# clink.net
KiCad netlist of a schematic drawn in EAGLE
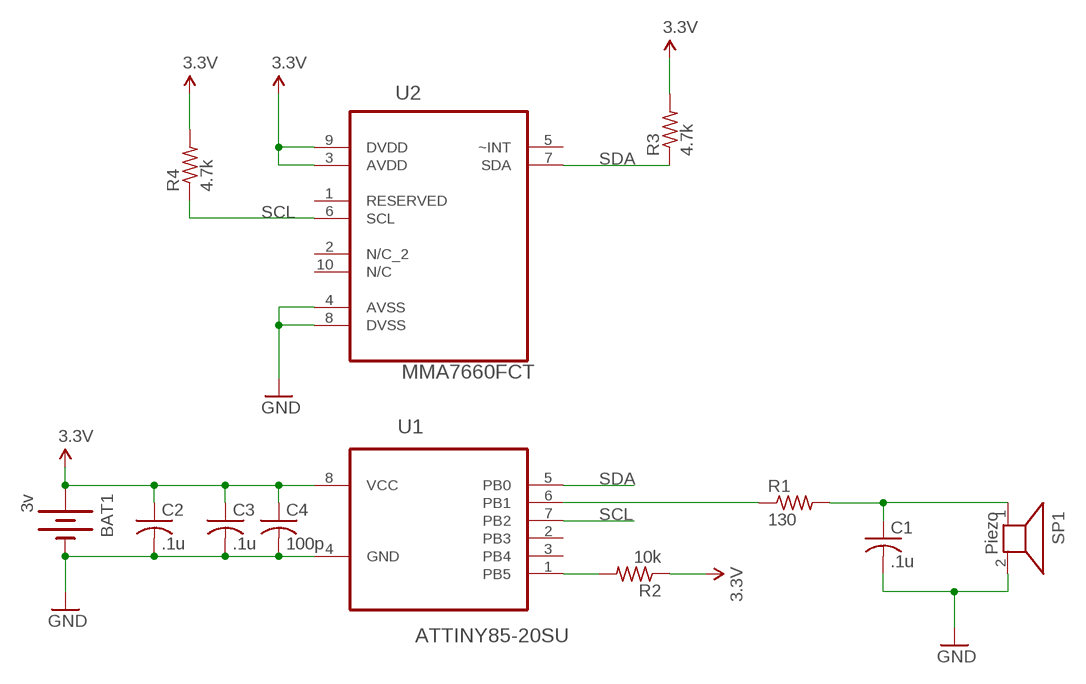
[diagram p0: schematic, sheet 1]

(export (version "E")
  (design (tool "Eeschema 10.0.6"))
  (components
    (comp (ref "BAT1")
      (value "3v")
      (footprint "eagle-import:BATTCON_20MM")
      (libsource (lib "eagle-import") (part "BATTERY20SMD"))
    )
    (comp (ref "C1")
      (value ".1u")
      (footprint "eagle-import:C0603")
      (libsource (lib "eagle-import") (part "C-USC0603"))
    )
    (comp (ref "C2")
      (value ".1u")
      (footprint "eagle-import:C0603")
      (libsource (lib "eagle-import") (part "C-USC0603"))
    )
    (comp (ref "C3")
      (value ".1u")
      (footprint "eagle-import:C0603")
      (libsource (lib "eagle-import") (part "C-USC0603"))
    )
    (comp (ref "C4")
      (value "100p")
      (footprint "eagle-import:C0603")
      (libsource (lib "eagle-import") (part "C-USC0603"))
    )
    (comp (ref "R1")
      (value "130")
      (footprint "eagle-import:R0603")
      (libsource (lib "eagle-import") (part "R-US_R0603"))
    )
    (comp (ref "R2")
      (value "10k")
      (footprint "eagle-import:R0603")
      (libsource (lib "eagle-import") (part "R-US_R0603"))
    )
    (comp (ref "R3")
      (value "4.7k")
      (footprint "eagle-import:R0603")
      (libsource (lib "eagle-import") (part "R-US_R0603"))
    )
    (comp (ref "R4")
      (value "4.7k")
      (footprint "eagle-import:R0603")
      (libsource (lib "eagle-import") (part "R-US_R0603"))
    )
    (comp (ref "SP1")
      (value "Piezo")
      (footprint "eagle-import:AL201P")
      (libsource (lib "eagle-import") (part "AL201P"))
    )
    (comp (ref "U1")
      (value "ATTINY85-20SU")
      (footprint "eagle-import:SOIC127P798X216-8N")
      (libsource (lib "eagle-import") (part "ATTINY85-20SU"))
    )
    (comp (ref "U2")
      (value "MMA7660FCT")
      (footprint "eagle-import:DFN300X300X100-10N")
      (libsource (lib "eagle-import") (part "MMA7660FCT"))
    )
  )
  (nets
    (net (code "1") (name "/SCL") (class "Default")
      (node (ref "R4") (pin "1") (pinfunction "1_1") (pintype "passive"))
      (node (ref "U1") (pin "7") (pinfunction "PB2_7") (pintype "bidirectional"))
      (node (ref "U2") (pin "6") (pinfunction "SCL_6") (pintype "input"))
    )
    (net (code "2") (name "/SDA") (class "Default")
      (node (ref "R3") (pin "1") (pinfunction "1_1") (pintype "passive"))
      (node (ref "U1") (pin "5") (pinfunction "PB0_5") (pintype "bidirectional"))
      (node (ref "U2") (pin "7") (pinfunction "SDA_7") (pintype "bidirectional"))
    )
    (net (code "3") (name "3.3V") (class "Default")
      (node (ref "BAT1") (pin "1") (pinfunction "+_1") (pintype "power_in"))
      (node (ref "C2") (pin "1") (pinfunction "1_1") (pintype "passive"))
      (node (ref "C3") (pin "1") (pinfunction "1_1") (pintype "passive"))
      (node (ref "C4") (pin "1") (pinfunction "1_1") (pintype "passive"))
      (node (ref "R2") (pin "1") (pinfunction "1_1") (pintype "passive"))
      (node (ref "R3") (pin "2") (pinfunction "2_2") (pintype "passive"))
      (node (ref "R4") (pin "2") (pinfunction "2_2") (pintype "passive"))
      (node (ref "U1") (pin "8") (pinfunction "VCC_8") (pintype "power_in"))
      (node (ref "U2") (pin "3") (pinfunction "AVDD_3") (pintype "power_in"))
      (node (ref "U2") (pin "9") (pinfunction "DVDD_9") (pintype "power_in"))
    )
    (net (code "4") (name "GND") (class "Default")
      (node (ref "BAT1") (pin "2") (pinfunction "-_2") (pintype "power_in"))
      (node (ref "C1") (pin "2") (pinfunction "2_2") (pintype "passive"))
      (node (ref "C2") (pin "2") (pinfunction "2_2") (pintype "passive"))
      (node (ref "C3") (pin "2") (pinfunction "2_2") (pintype "passive"))
      (node (ref "C4") (pin "2") (pinfunction "2_2") (pintype "passive"))
      (node (ref "SP1") (pin "2") (pinfunction "2_2") (pintype "passive"))
      (node (ref "U1") (pin "4") (pinfunction "GND_4") (pintype "passive"))
      (node (ref "U2") (pin "4") (pinfunction "AVSS_4") (pintype "power_in"))
      (node (ref "U2") (pin "8") (pinfunction "DVSS_8") (pintype "power_in"))
    )
    (net (code "5") (name "Net-(C1-Pad1)") (class "Default")
      (node (ref "C1") (pin "1") (pinfunction "1_1") (pintype "passive"))
      (node (ref "R1") (pin "2") (pinfunction "2_2") (pintype "passive"))
      (node (ref "SP1") (pin "1") (pinfunction "1_1") (pintype "passive"))
    )
    (net (code "6") (name "Net-(U1-PB1)") (class "Default")
      (node (ref "R1") (pin "1") (pinfunction "1_1") (pintype "passive"))
      (node (ref "U1") (pin "6") (pinfunction "PB1_6") (pintype "bidirectional"))
    )
    (net (code "7") (name "Net-(U1-PB5)") (class "Default")
      (node (ref "R2") (pin "2") (pinfunction "2_2") (pintype "passive"))
      (node (ref "U1") (pin "1") (pinfunction "PB5_1") (pintype "bidirectional"))
    )
    (net (code "8") (name "unconnected-(U1-PB3-Pad2)") (class "Default")
      (node (ref "U1") (pin "2") (pinfunction "PB3_2") (pintype "bidirectional"))
    )
    (net (code "9") (name "unconnected-(U1-PB4-Pad3)") (class "Default")
      (node (ref "U1") (pin "3") (pinfunction "PB4_3") (pintype "bidirectional"))
    )
    (net (code "10") (name "unconnected-(U2-N{slash}C-Pad10)") (class "Default")
      (node (ref "U2") (pin "10") (pinfunction "N/C_10") (pintype "no_connect"))
    )
    (net (code "11") (name "unconnected-(U2-N{slash}C_2-Pad2)") (class "Default")
      (node (ref "U2") (pin "2") (pinfunction "N/C_2_2") (pintype "no_connect"))
    )
    (net (code "12") (name "unconnected-(U2-RESERVED-Pad1)") (class "Default")
      (node (ref "U2") (pin "1") (pinfunction "RESERVED_1") (pintype "passive"))
    )
    (net (code "13") (name "unconnected-(U2-~{INT}-Pad5)") (class "Default")
      (node (ref "U2") (pin "5") (pinfunction "~{INT}_5") (pintype "output"))
    )
  )
)
